# Motor_driver.net
KiCad netlist of a schematic drawn in Altium Designer
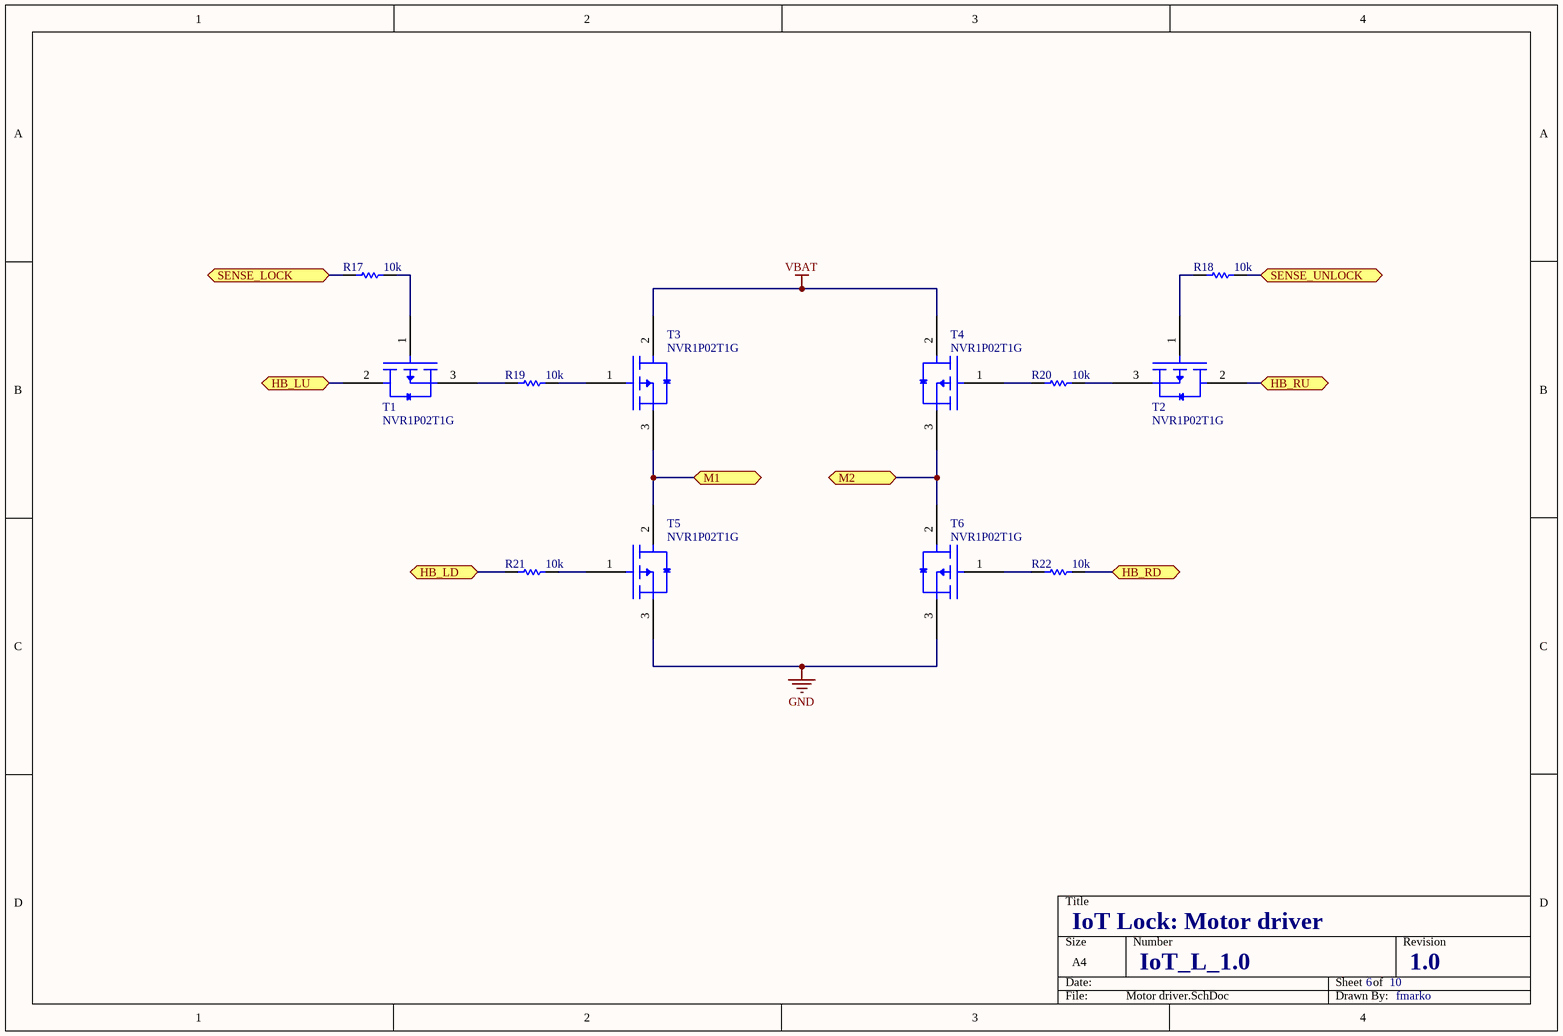
[diagram p0: Motor driver.SchDoc]

(export (version "E")
  (design (tool "Eeschema 10.0.6"))
  (components
    (comp (ref "R17")
      (value "10k")
      (footprint "0402")
      (description "Semiconductor Resistor")
      (fields (field (name "Comment") "Res Semi") (field (name "PUBLISHER") "Altium Limited"))
      (libsource (lib "Miscellaneous Devices") (part "Res Semi"))
    )
    (comp (ref "R18")
      (value "10k")
      (footprint "0402")
      (description "Semiconductor Resistor")
      (fields (field (name "Comment") "Res Semi") (field (name "PUBLISHER") "Altium Limited"))
      (libsource (lib "Miscellaneous Devices") (part "Res Semi"))
    )
    (comp (ref "R19")
      (value "10k")
      (footprint "0402")
      (description "Semiconductor Resistor")
      (fields (field (name "Comment") "Res Semi") (field (name "PUBLISHER") "Altium Limited"))
      (libsource (lib "Miscellaneous Devices") (part "Res Semi"))
    )
    (comp (ref "R20")
      (value "10k")
      (footprint "0402")
      (description "Semiconductor Resistor")
      (fields (field (name "Comment") "Res Semi") (field (name "PUBLISHER") "Altium Limited"))
      (libsource (lib "Miscellaneous Devices") (part "Res Semi"))
    )
    (comp (ref "R21")
      (value "10k")
      (footprint "0402")
      (description "Semiconductor Resistor")
      (fields (field (name "Comment") "Res Semi") (field (name "PUBLISHER") "Altium Limited"))
      (libsource (lib "Miscellaneous Devices") (part "Res Semi"))
    )
    (comp (ref "R22")
      (value "10k")
      (footprint "0402")
      (description "Semiconductor Resistor")
      (fields (field (name "Comment") "Res Semi") (field (name "PUBLISHER") "Altium Limited"))
      (libsource (lib "Miscellaneous Devices") (part "Res Semi"))
    )
    (comp (ref "T1")
      (value "NVR1P02T1G")
      (footprint "SOT95P237X111-3N")
      (description "P-Channel MOSFET")
      (libsource (lib "NVR1P02T1G") (part "NVR1P02T1G"))
    )
    (comp (ref "T2")
      (value "NVR1P02T1G")
      (footprint "SOT95P237X111-3N")
      (description "P-Channel MOSFET")
      (libsource (lib "NVR1P02T1G") (part "NVR1P02T1G"))
    )
    (comp (ref "T3")
      (value "NVR1P02T1G")
      (footprint "SOT95P237X111-3N")
      (description "P-Channel MOSFET")
      (libsource (lib "NVR1P02T1G") (part "NVR1P02T1G"))
    )
    (comp (ref "T4")
      (value "NVR1P02T1G")
      (footprint "SOT95P237X111-3N")
      (description "P-Channel MOSFET")
      (libsource (lib "NVR1P02T1G") (part "NVR1P02T1G"))
    )
    (comp (ref "T5")
      (value "NVR1P02T1G")
      (footprint "SOT95P237X111-3N")
      (description "P-Channel MOSFET")
      (libsource (lib "NVR1P02T1G") (part "NVR1P02T1G"))
    )
    (comp (ref "T6")
      (value "NVR1P02T1G")
      (footprint "SOT95P237X111-3N")
      (description "P-Channel MOSFET")
      (libsource (lib "NVR1P02T1G") (part "NVR1P02T1G"))
    )
  )
  (nets
    (net (code "1") (name "/HB_LD") (class "Default")
      (node (ref "R21") (pin "1") (pinfunction "1_1") (pintype "passive"))
    )
    (net (code "2") (name "/HB_LU") (class "Default")
      (node (ref "T1") (pin "2") (pinfunction "S_2") (pintype "passive"))
    )
    (net (code "3") (name "/HB_RD") (class "Default")
      (node (ref "R22") (pin "2") (pinfunction "2_2") (pintype "passive"))
    )
    (net (code "4") (name "/HB_RU") (class "Default")
      (node (ref "T2") (pin "2") (pinfunction "S_2") (pintype "passive"))
    )
    (net (code "5") (name "/M1") (class "Default")
      (node (ref "T3") (pin "3") (pinfunction "D_3") (pintype "passive"))
      (node (ref "T5") (pin "2") (pinfunction "S_2") (pintype "passive"))
    )
    (net (code "6") (name "/M2") (class "Default")
      (node (ref "T4") (pin "3") (pinfunction "D_3") (pintype "passive"))
      (node (ref "T6") (pin "2") (pinfunction "S_2") (pintype "passive"))
    )
    (net (code "7") (name "/SENSE_LOCK") (class "Default")
      (node (ref "R17") (pin "1") (pinfunction "1_1") (pintype "passive"))
    )
    (net (code "8") (name "/SENSE_UNLOCK") (class "Default")
      (node (ref "R18") (pin "2") (pinfunction "2_2") (pintype "passive"))
    )
    (net (code "9") (name "GND") (class "Default")
      (node (ref "T5") (pin "3") (pinfunction "D_3") (pintype "passive"))
      (node (ref "T6") (pin "3") (pinfunction "D_3") (pintype "passive"))
    )
    (net (code "10") (name "Net-(T1-D)") (class "Default")
      (node (ref "R19") (pin "1") (pinfunction "1_1") (pintype "passive"))
      (node (ref "T1") (pin "3") (pinfunction "D_3") (pintype "passive"))
    )
    (net (code "11") (name "Net-(T1-G)") (class "Default")
      (node (ref "R17") (pin "2") (pinfunction "2_2") (pintype "passive"))
      (node (ref "T1") (pin "1") (pinfunction "G_1") (pintype "passive"))
    )
    (net (code "12") (name "Net-(T2-D)") (class "Default")
      (node (ref "R20") (pin "2") (pinfunction "2_2") (pintype "passive"))
      (node (ref "T2") (pin "3") (pinfunction "D_3") (pintype "passive"))
    )
    (net (code "13") (name "Net-(T2-G)") (class "Default")
      (node (ref "R18") (pin "1") (pinfunction "1_1") (pintype "passive"))
      (node (ref "T2") (pin "1") (pinfunction "G_1") (pintype "passive"))
    )
    (net (code "14") (name "Net-(T3-G)") (class "Default")
      (node (ref "R19") (pin "2") (pinfunction "2_2") (pintype "passive"))
      (node (ref "T3") (pin "1") (pinfunction "G_1") (pintype "passive"))
    )
    (net (code "15") (name "Net-(T4-G)") (class "Default")
      (node (ref "R20") (pin "1") (pinfunction "1_1") (pintype "passive"))
      (node (ref "T4") (pin "1") (pinfunction "G_1") (pintype "passive"))
    )
    (net (code "16") (name "Net-(T5-G)") (class "Default")
      (node (ref "R21") (pin "2") (pinfunction "2_2") (pintype "passive"))
      (node (ref "T5") (pin "1") (pinfunction "G_1") (pintype "passive"))
    )
    (net (code "17") (name "Net-(T6-G)") (class "Default")
      (node (ref "R22") (pin "1") (pinfunction "1_1") (pintype "passive"))
      (node (ref "T6") (pin "1") (pinfunction "G_1") (pintype "passive"))
    )
    (net (code "18") (name "VBAT") (class "Default")
      (node (ref "T3") (pin "2") (pinfunction "S_2") (pintype "passive"))
      (node (ref "T4") (pin "2") (pinfunction "S_2") (pintype "passive"))
    )
  )
)
